# Schametic.net
KiCad netlist of a schematic drawn in EasyEDA
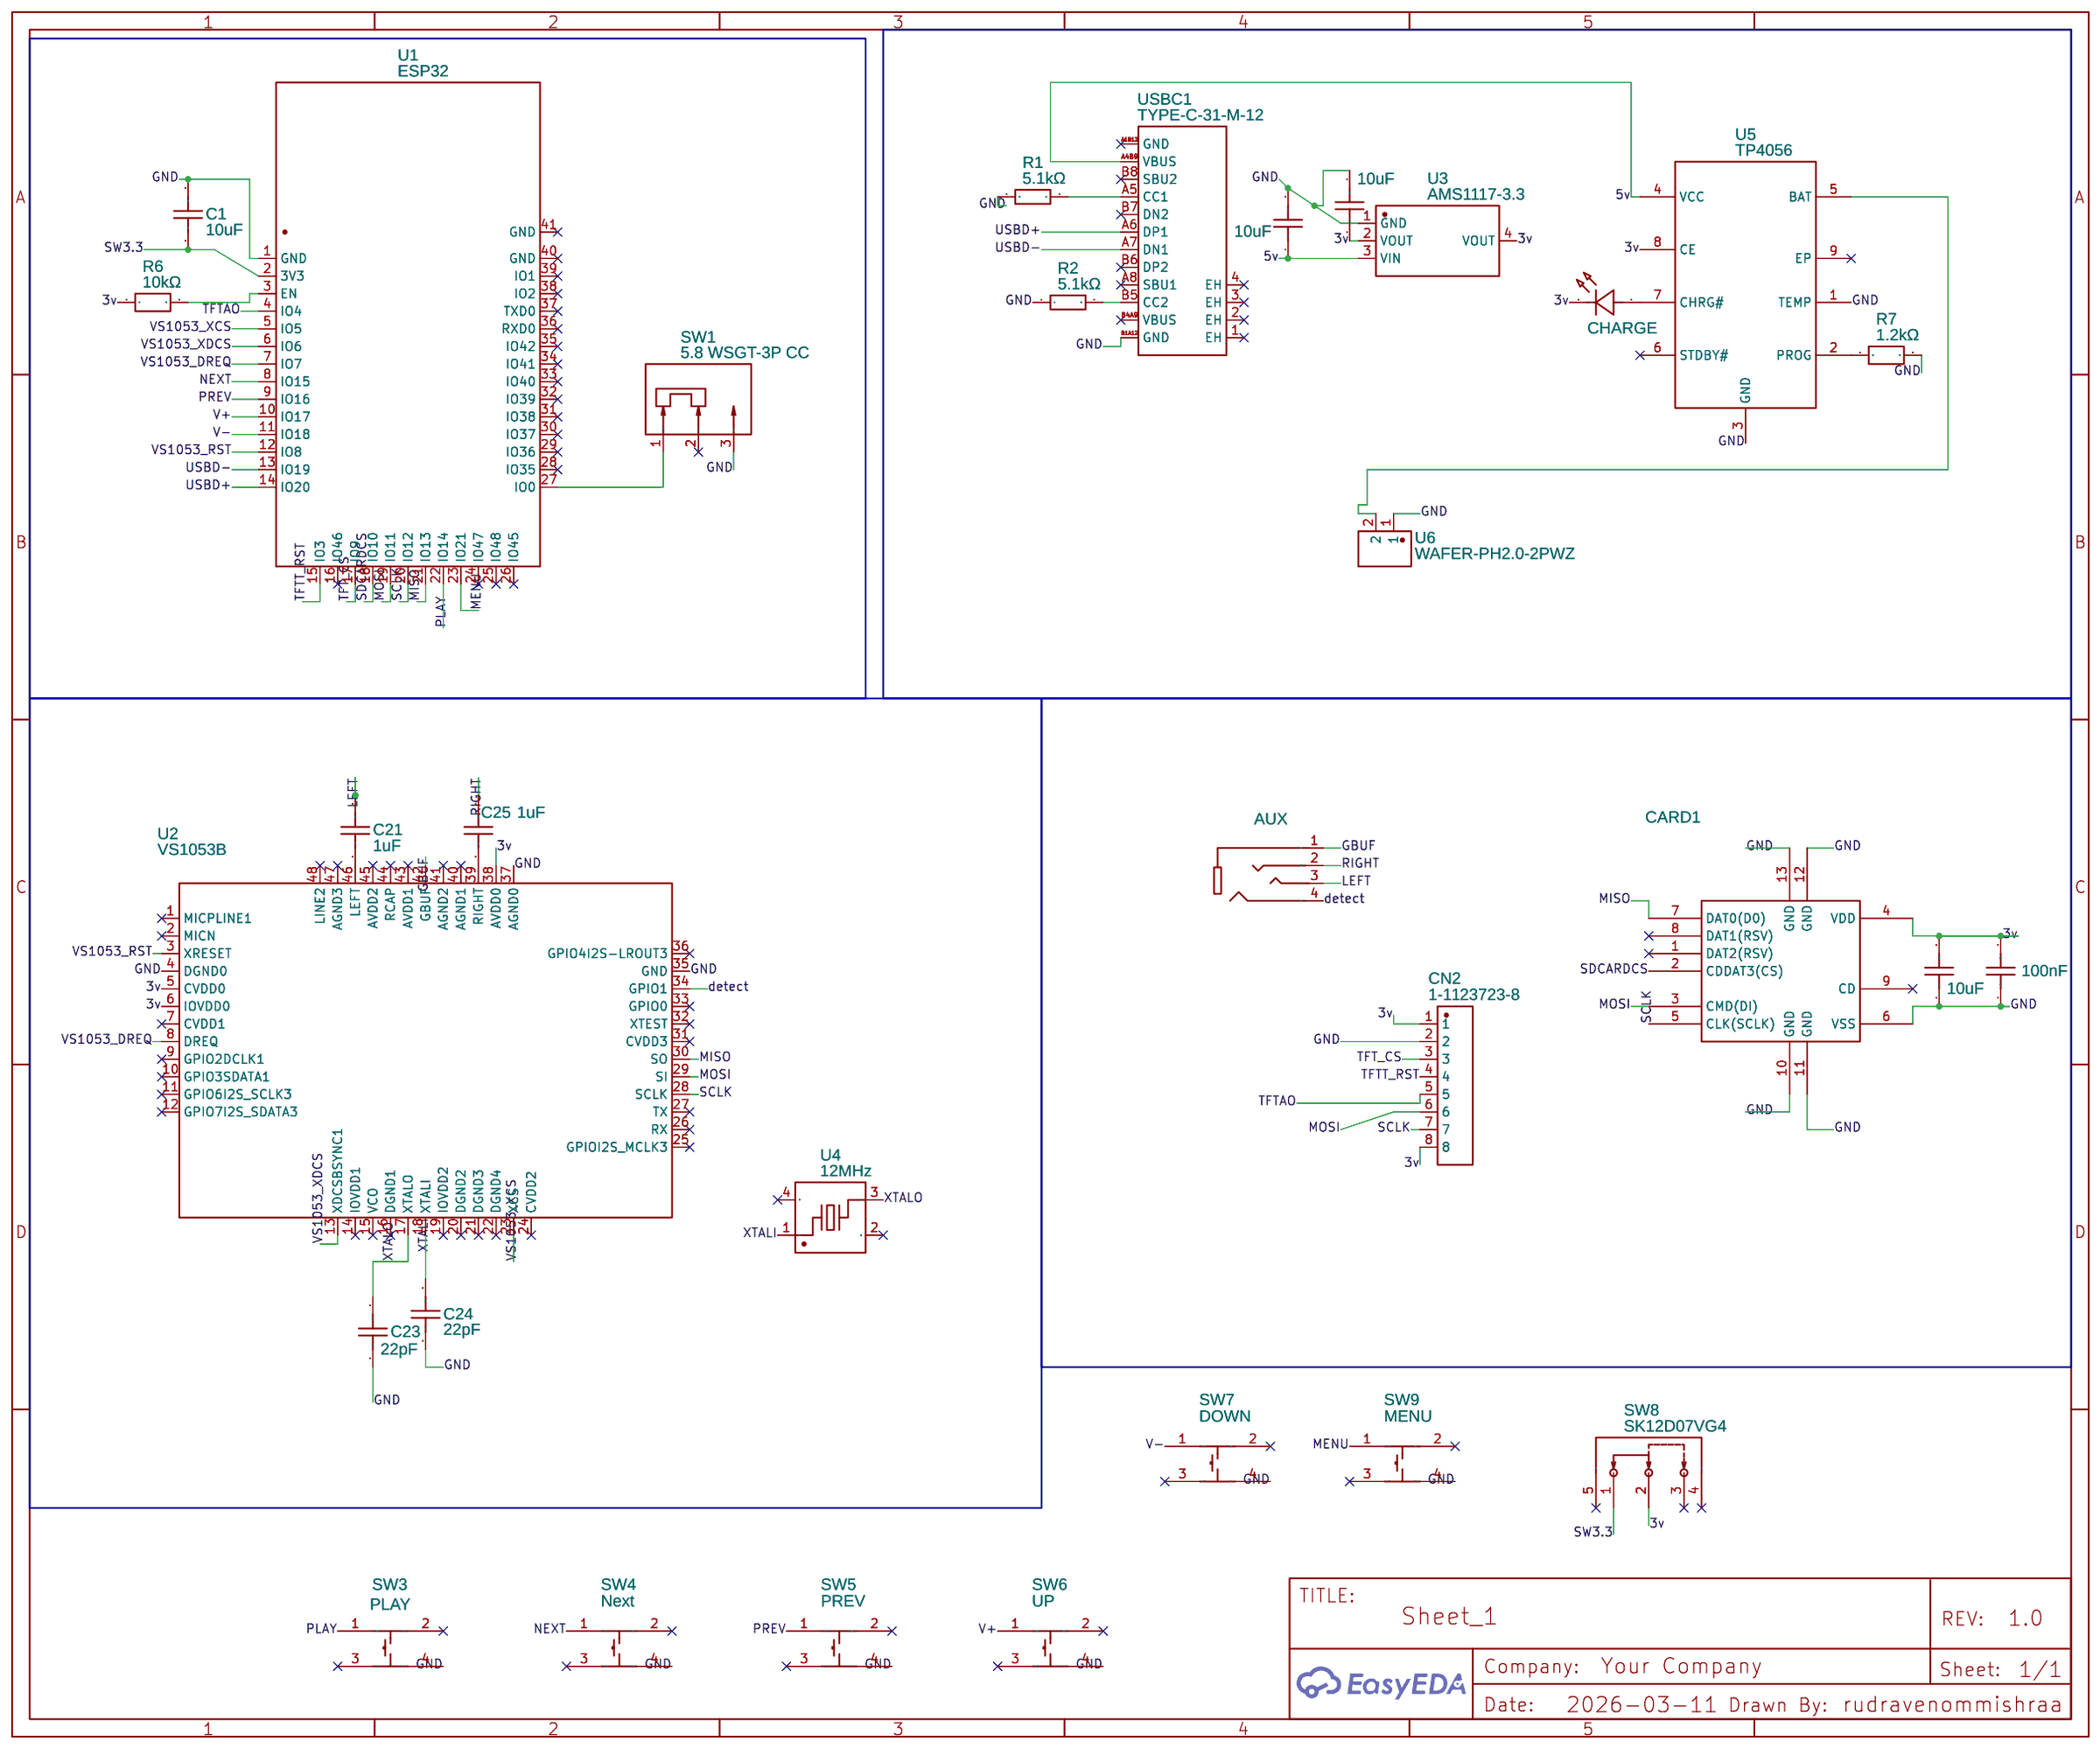
[diagram p0: schematic sheet]

(export (version "E")
  (design (tool "Eeschema 10.0.6"))
  (components
    (comp (ref "C1")
      (value "10uF")
      (fields
        (field (name "Manufacturer Part") "CL10A106KP8NNNC")
        (field (name "Manufacturer") "SAMSUNG(三星)")
      )
      (libsource (lib "") (part "CL10A106KP8NNNC"))
    )
    (comp (ref "C2")
      (value "10uF")
      (fields
        (field (name "Manufacturer Part") "CL10A106KP8NNNC")
        (field (name "Manufacturer") "SAMSUNG(三星)")
      )
      (libsource (lib "") (part "CL10A106KP8NNNC"))
    )
    (comp (ref "C7")
      (value "100nF")
      (fields
        (field (name "Manufacturer Part") "CC0603KRX7R9BB104")
        (field (name "Manufacturer") "YAGEO(国巨)")
      )
      (libsource (lib "") (part "CC0603KRX7R9BB104"))
    )
    (comp (ref "C9")
      (value "10uF")
      (fields
        (field (name "Manufacturer Part") "CL10A106KP8NNNC")
        (field (name "Manufacturer") "SAMSUNG(三星)")
      )
      (libsource (lib "") (part "CL10A106KP8NNNC"))
    )
    (comp (ref "C10")
      (value "10uF")
      (fields
        (field (name "Manufacturer Part") "CL10A106KP8NNNC")
        (field (name "Manufacturer") "SAMSUNG(三星)")
      )
      (libsource (lib "") (part "CL10A106KP8NNNC"))
    )
    (comp (ref "C21")
      (value "1uF")
      (fields
        (field (name "Manufacturer Part") "CL10A105KB8NNNC")
        (field (name "Manufacturer") "SAMSUNG(三星)")
      )
      (libsource (lib "") (part "CL10A105KB8NNNC_1"))
    )
    (comp (ref "C23")
      (value "22pF")
      (fields (field (name "Manufacturer Part") "04025A220KAT2A") (field (name "Manufacturer") "Kyocera AVX"))
      (libsource (lib "") (part "04025A220KAT2A"))
    )
    (comp (ref "C24")
      (value "22pF")
      (fields (field (name "Manufacturer Part") "04025A220KAT2A") (field (name "Manufacturer") "Kyocera AVX"))
      (libsource (lib "") (part "04025A220KAT2A"))
    )
    (comp (ref "C25")
      (value "1uF")
      (fields
        (field (name "Manufacturer Part") "CL10A105KB8NNNC")
        (field (name "Manufacturer") "SAMSUNG(三星)")
      )
      (libsource (lib "") (part "CL10A105KB8NNNC"))
    )
    (comp (ref "CARD1")
      (value "TF-01A")
      (fields (field (name "Manufacturer") "韩国韩荣"))
      (libsource (lib "") (part "TF-01A"))
    )
    (comp (ref "CHARGE")
      (value "15-21SURC/S530-A3/3T")
      (fields (field (name "Manufacturer") "EVERLIGHT(亿光)"))
      (libsource (lib "") (part "15-21SURC/S530-A3/3T"))
    )
    (comp (ref "CN1")
      (value "AUX")
      (fields (field (name "Manufacturer Part") "HC-PJ-320A") (field (name "Manufacturer") "HC(虹成电子)"))
      (libsource (lib "") (part "HC-PJ-320A"))
    )
    (comp (ref "CN2")
      (value "1-1123723-8")
      (fields (field (name "Manufacturer") "TE Connectivity(泰科电子)"))
      (libsource (lib "") (part "1-1123723-8"))
    )
    (comp (ref "R1")
      (value "5.1kΩ")
      (fields
        (field (name "Manufacturer Part") "0603WAF5101T5E")
        (field (name "Manufacturer") "UNI-ROYAL(厚声)")
      )
      (libsource (lib "") (part "0603WAF5101T5E"))
    )
    (comp (ref "R2")
      (value "5.1kΩ")
      (fields
        (field (name "Manufacturer Part") "0603WAF5101T5E")
        (field (name "Manufacturer") "UNI-ROYAL(厚声)")
      )
      (libsource (lib "") (part "0603WAF5101T5E"))
    )
    (comp (ref "R6")
      (value "10kΩ")
      (fields (field (name "Manufacturer Part") "SCR0603J10K") (field (name "Manufacturer") "VO(翔胜)"))
      (libsource (lib "") (part "SCR0603J10K"))
    )
    (comp (ref "R7")
      (value "1.2kΩ")
      (fields
        (field (name "Manufacturer Part") "0603WAD1201T5E")
        (field (name "Manufacturer") "UNI-ROYAL(厚声)")
      )
      (libsource (lib "") (part "0603WAD1201T5E"))
    )
    (comp (ref "SW1")
      (value "5.8 WSGT-3P CC")
      (fields (field (name "Manufacturer") "SHOU HAN(首韩)"))
      (libsource (lib "") (part "5.8 WSGT-3P CC"))
    )
    (comp (ref "SW3")
      (value "PLAY")
      (fields (field (name "Manufacturer Part") "TS-1002S-07026C") (field (name "Manufacturer") "XUNPU(讯普)"))
      (libsource (lib "") (part "TS-1002S-07026C"))
    )
    (comp (ref "SW4")
      (value "Next")
      (fields (field (name "Manufacturer Part") "TS-1002S-07026C") (field (name "Manufacturer") "XUNPU(讯普)"))
      (libsource (lib "") (part "TS-1002S-07026C"))
    )
    (comp (ref "SW5")
      (value "PREV")
      (fields (field (name "Manufacturer Part") "TS-1002S-07026C") (field (name "Manufacturer") "XUNPU(讯普)"))
      (libsource (lib "") (part "TS-1002S-07026C"))
    )
    (comp (ref "SW6")
      (value "UP")
      (fields (field (name "Manufacturer Part") "TS-1002S-07026C") (field (name "Manufacturer") "XUNPU(讯普)"))
      (libsource (lib "") (part "TS-1002S-07026C"))
    )
    (comp (ref "SW7")
      (value "DOWN")
      (fields (field (name "Manufacturer Part") "TS-1002S-07026C") (field (name "Manufacturer") "XUNPU(讯普)"))
      (libsource (lib "") (part "TS-1002S-07026C"))
    )
    (comp (ref "SW8")
      (value "SK12D07VG4")
      (fields (field (name "Manufacturer") "SHOU HAN(首韩)"))
      (libsource (lib "") (part "SK12D07VG4"))
    )
    (comp (ref "SW9")
      (value "MENU")
      (fields (field (name "Manufacturer Part") "TS-1002S-07026C") (field (name "Manufacturer") "XUNPU(讯普)"))
      (libsource (lib "") (part "TS-1002S-07026C"))
    )
    (comp (ref "U1")
      (value "ESP32")
      (fields
        (field (name "Manufacturer Part") "ESP32-S3-WROOM-1-N16R8")
        (field (name "Manufacturer") "ESPRESSIF(乐鑫)")
      )
      (libsource (lib "") (part "ESP32-S3-WROOM-1(N16R8)"))
    )
    (comp (ref "U2")
      (value "VS1053B")
      (fields (field (name "Manufacturer Part") "VS1053B-L") (field (name "Manufacturer") "VLSI"))
      (libsource (lib "") (part "VS1053B"))
    )
    (comp (ref "U3")
      (value "AMS1117-3.3")
      (fields (field (name "Manufacturer") "AMS"))
      (libsource (lib "") (part "AMS1117-3.3"))
    )
    (comp (ref "U4")
      (value "12MHz")
      (fields
        (field (name "Manufacturer Part") "01.X.MH.120HHRI0012000000")
        (field (name "Manufacturer") "CREC(晶宝)")
      )
      (libsource (lib "") (part "01.X.MH.120HHRI0012000000"))
    )
    (comp (ref "U5")
      (value "TP4056")
      (fields
        (field (name "Manufacturer Part") "TP4056-42-ESOP8")
        (field (name "Manufacturer") "TOPPOWER(南京拓微)")
      )
      (libsource (lib "") (part "TP4056"))
    )
    (comp (ref "U6")
      (value "WAFER-PH2.0-2PWZ")
      (fields (field (name "Manufacturer") "XUNPU(讯普)"))
      (libsource (lib "") (part "WAFER-PH2.0-2PWZ"))
    )
    (comp (ref "USBC1")
      (value "TYPE-C-31-M-12")
      (fields (field (name "Manufacturer") "韩国韩荣"))
      (libsource (lib "") (part "TYPE-C-31-M-12"))
    )
  )
  (nets
    (net (code "1") (name "/3v") (class "Default")
      (node (ref "C10") (pin "1") (pinfunction "1_1") (pintype "unspecified"))
      (node (ref "C2") (pin "2") (pinfunction "2_2") (pintype "unspecified"))
      (node (ref "C7") (pin "2") (pinfunction "2_2") (pintype "unspecified"))
      (node (ref "CARD1") (pin "4") (pinfunction "VDD_4") (pintype "input"))
      (node (ref "CHARGE") (pin "2") (pinfunction "K_2") (pintype "unspecified"))
      (node (ref "CN2") (pin "1") (pinfunction "1_1") (pintype "unspecified"))
      (node (ref "CN2") (pin "8") (pinfunction "8_8") (pintype "unspecified"))
      (node (ref "R6") (pin "1") (pinfunction "1_1") (pintype "unspecified"))
      (node (ref "SW8") (pin "2") (pinfunction "2_2") (pintype "unspecified"))
      (node (ref "U2") (pin "38") (pinfunction "AVDD0_38") (pintype "unspecified"))
      (node (ref "U2") (pin "5") (pinfunction "CVDD0_5") (pintype "passive"))
      (node (ref "U2") (pin "6") (pinfunction "IOVDD0_6") (pintype "passive"))
      (node (ref "U3") (pin "2") (pinfunction "VOUT_2") (pintype "unspecified"))
      (node (ref "U3") (pin "4") (pinfunction "VOUT_4") (pintype "unspecified"))
      (node (ref "U5") (pin "8") (pinfunction "CE_8") (pintype "unspecified"))
    )
    (net (code "2") (name "/5v") (class "Default")
      (node (ref "C9") (pin "1") (pinfunction "1_1") (pintype "unspecified"))
      (node (ref "U3") (pin "3") (pinfunction "VIN_3") (pintype "unspecified"))
      (node (ref "U5") (pin "4") (pinfunction "VCC_4") (pintype "unspecified"))
      (node (ref "USBC1") (pin "A4B9") (pinfunction "VBUS_A4B9") (pintype "unspecified"))
    )
    (net (code "3") (name "/GBUF") (class "Default")
      (node (ref "CN1") (pin "1") (pinfunction "1_1") (pintype "unspecified"))
      (node (ref "U2") (pin "42") (pinfunction "GBUF_42") (pintype "unspecified"))
    )
    (net (code "4") (name "/GND") (class "Default")
      (node (ref "C1") (pin "2") (pinfunction "2_2") (pintype "unspecified"))
      (node (ref "C10") (pin "2") (pinfunction "2_2") (pintype "unspecified"))
      (node (ref "C2") (pin "1") (pinfunction "1_1") (pintype "unspecified"))
      (node (ref "C23") (pin "1") (pinfunction "1_1") (pintype "unspecified"))
      (node (ref "C24") (pin "1") (pinfunction "1_1") (pintype "unspecified"))
      (node (ref "C7") (pin "1") (pinfunction "1_1") (pintype "unspecified"))
      (node (ref "C9") (pin "2") (pinfunction "2_2") (pintype "unspecified"))
      (node (ref "CARD1") (pin "10") (pinfunction "GND_10") (pintype "input"))
      (node (ref "CARD1") (pin "11") (pinfunction "GND_11") (pintype "input"))
      (node (ref "CARD1") (pin "12") (pinfunction "GND_12") (pintype "input"))
      (node (ref "CARD1") (pin "13") (pinfunction "GND_13") (pintype "input"))
      (node (ref "CARD1") (pin "6") (pinfunction "VSS_6") (pintype "input"))
      (node (ref "CN2") (pin "2") (pinfunction "2_2") (pintype "unspecified"))
      (node (ref "R1") (pin "1") (pinfunction "1_1") (pintype "input"))
      (node (ref "R2") (pin "1") (pinfunction "1_1") (pintype "input"))
      (node (ref "R7") (pin "2") (pinfunction "2_2") (pintype "unspecified"))
      (node (ref "SW1") (pin "3") (pinfunction "3_3") (pintype "unspecified"))
      (node (ref "SW3") (pin "4") (pinfunction "4_4") (pintype "unspecified"))
      (node (ref "SW4") (pin "4") (pinfunction "4_4") (pintype "unspecified"))
      (node (ref "SW5") (pin "4") (pinfunction "4_4") (pintype "unspecified"))
      (node (ref "SW6") (pin "4") (pinfunction "4_4") (pintype "unspecified"))
      (node (ref "SW7") (pin "4") (pinfunction "4_4") (pintype "unspecified"))
      (node (ref "SW9") (pin "4") (pinfunction "4_4") (pintype "unspecified"))
      (node (ref "U1") (pin "1") (pinfunction "GND_1") (pintype "unspecified"))
      (node (ref "U2") (pin "35") (pinfunction "GND_35") (pintype "unspecified"))
      (node (ref "U2") (pin "37") (pinfunction "AGND0_37") (pintype "unspecified"))
      (node (ref "U2") (pin "4") (pinfunction "DGND0_4") (pintype "unspecified"))
      (node (ref "U3") (pin "1") (pinfunction "GND_1") (pintype "unspecified"))
      (node (ref "U5") (pin "1") (pinfunction "TEMP_1") (pintype "unspecified"))
      (node (ref "U5") (pin "3") (pinfunction "GND_3") (pintype "unspecified"))
      (node (ref "U6") (pin "1") (pinfunction "1_1") (pintype "unspecified"))
      (node (ref "USBC1") (pin "B1A12") (pinfunction "GND_B1A12") (pintype "unspecified"))
    )
    (net (code "5") (name "/LEFT") (class "Default")
      (node (ref "C21") (pin "2") (pinfunction "2_2") (pintype "unspecified"))
      (node (ref "CN1") (pin "3") (pinfunction "3_3") (pintype "unspecified"))
    )
    (net (code "6") (name "/MENU") (class "Default")
      (node (ref "SW9") (pin "1") (pinfunction "1_1") (pintype "unspecified"))
      (node (ref "U1") (pin "23") (pinfunction "IO21_23") (pintype "unspecified"))
    )
    (net (code "7") (name "/MISO") (class "Default")
      (node (ref "CARD1") (pin "7") (pinfunction "DAT0(D0)_7") (pintype "bidirectional"))
      (node (ref "U1") (pin "21") (pinfunction "IO13_21") (pintype "unspecified"))
      (node (ref "U2") (pin "30") (pinfunction "SO_30") (pintype "unspecified"))
    )
    (net (code "8") (name "/MOSI") (class "Default")
      (node (ref "CARD1") (pin "3") (pinfunction "CMD(DI)_3") (pintype "input"))
      (node (ref "CN2") (pin "6") (pinfunction "6_6") (pintype "unspecified"))
      (node (ref "U1") (pin "19") (pinfunction "IO11_19") (pintype "unspecified"))
      (node (ref "U2") (pin "29") (pinfunction "SI_29") (pintype "unspecified"))
    )
    (net (code "9") (name "/NEXT") (class "Default")
      (node (ref "SW4") (pin "1") (pinfunction "1_1") (pintype "unspecified"))
      (node (ref "U1") (pin "8") (pinfunction "IO15_8") (pintype "unspecified"))
    )
    (net (code "10") (name "/PLAY") (class "Default")
      (node (ref "SW3") (pin "1") (pinfunction "1_1") (pintype "unspecified"))
      (node (ref "U1") (pin "22") (pinfunction "IO14_22") (pintype "unspecified"))
    )
    (net (code "11") (name "/PREV") (class "Default")
      (node (ref "SW5") (pin "1") (pinfunction "1_1") (pintype "unspecified"))
      (node (ref "U1") (pin "9") (pinfunction "IO16_9") (pintype "unspecified"))
    )
    (net (code "12") (name "/RIGHT") (class "Default")
      (node (ref "C25") (pin "1") (pinfunction "1_1") (pintype "unspecified"))
      (node (ref "CN1") (pin "2") (pinfunction "2_2") (pintype "unspecified"))
    )
    (net (code "13") (name "/SCLK") (class "Default")
      (node (ref "CARD1") (pin "5") (pinfunction "CLK(SCLK)_5") (pintype "input"))
      (node (ref "CN2") (pin "7") (pinfunction "7_7") (pintype "unspecified"))
      (node (ref "U1") (pin "20") (pinfunction "IO12_20") (pintype "unspecified"))
      (node (ref "U2") (pin "28") (pinfunction "SCLK_28") (pintype "unspecified"))
    )
    (net (code "14") (name "/SDCARDCS") (class "Default")
      (node (ref "CARD1") (pin "2") (pinfunction "CDDAT3(CS)_2") (pintype "bidirectional"))
      (node (ref "U1") (pin "18") (pinfunction "IO10_18") (pintype "unspecified"))
    )
    (net (code "15") (name "/SW3.3") (class "Default")
      (node (ref "C1") (pin "1") (pinfunction "1_1") (pintype "unspecified"))
      (node (ref "SW8") (pin "1") (pinfunction "1_1") (pintype "unspecified"))
      (node (ref "U1") (pin "2") (pinfunction "3V3_2") (pintype "unspecified"))
    )
    (net (code "16") (name "/TFTAO") (class "Default")
      (node (ref "CN2") (pin "5") (pinfunction "5_5") (pintype "unspecified"))
      (node (ref "U1") (pin "4") (pinfunction "IO4_4") (pintype "unspecified"))
    )
    (net (code "17") (name "/TFTT_RST") (class "Default")
      (node (ref "CN2") (pin "4") (pinfunction "4_4") (pintype "unspecified"))
      (node (ref "U1") (pin "15") (pinfunction "IO3_15") (pintype "unspecified"))
    )
    (net (code "18") (name "/TFT_CS") (class "Default")
      (node (ref "CN2") (pin "3") (pinfunction "3_3") (pintype "unspecified"))
      (node (ref "U1") (pin "17") (pinfunction "IO9_17") (pintype "unspecified"))
    )
    (net (code "19") (name "/USBD+") (class "Default")
      (node (ref "U1") (pin "14") (pinfunction "IO20_14") (pintype "unspecified"))
      (node (ref "USBC1") (pin "A6") (pinfunction "DP1_A6") (pintype "unspecified"))
    )
    (net (code "20") (name "/USBD-") (class "Default")
      (node (ref "U1") (pin "13") (pinfunction "IO19_13") (pintype "unspecified"))
      (node (ref "USBC1") (pin "A7") (pinfunction "DN1_A7") (pintype "unspecified"))
    )
    (net (code "21") (name "/V+") (class "Default")
      (node (ref "SW6") (pin "1") (pinfunction "1_1") (pintype "unspecified"))
      (node (ref "U1") (pin "10") (pinfunction "IO17_10") (pintype "unspecified"))
    )
    (net (code "22") (name "/V-") (class "Default")
      (node (ref "SW7") (pin "1") (pinfunction "1_1") (pintype "unspecified"))
      (node (ref "U1") (pin "11") (pinfunction "IO18_11") (pintype "unspecified"))
    )
    (net (code "23") (name "/VS1053_DREQ") (class "Default")
      (node (ref "U1") (pin "7") (pinfunction "IO7_7") (pintype "unspecified"))
      (node (ref "U2") (pin "8") (pinfunction "DREQ_8") (pintype "unspecified"))
    )
    (net (code "24") (name "/VS1053_RST") (class "Default")
      (node (ref "U1") (pin "12") (pinfunction "IO8_12") (pintype "unspecified"))
      (node (ref "U2") (pin "3") (pinfunction "XRESET_3") (pintype "unspecified"))
    )
    (net (code "25") (name "/VS1053_XCS") (class "Default")
      (node (ref "U1") (pin "5") (pinfunction "IO5_5") (pintype "unspecified"))
      (node (ref "U2") (pin "23") (pinfunction "XCS_23") (pintype "unspecified"))
    )
    (net (code "26") (name "/VS1053_XDCS") (class "Default")
      (node (ref "U1") (pin "6") (pinfunction "IO6_6") (pintype "unspecified"))
      (node (ref "U2") (pin "13") (pinfunction "XDCSBSYNC1_13") (pintype "unspecified"))
    )
    (net (code "27") (name "/XTALI") (class "Default")
      (node (ref "C24") (pin "2") (pinfunction "2_2") (pintype "unspecified"))
      (node (ref "U2") (pin "18") (pinfunction "XTALI_18") (pintype "unspecified"))
      (node (ref "U4") (pin "1") (pinfunction "1_1") (pintype "input"))
    )
    (net (code "28") (name "/XTALO") (class "Default")
      (node (ref "C23") (pin "2") (pinfunction "2_2") (pintype "unspecified"))
      (node (ref "U2") (pin "17") (pinfunction "XTALO_17") (pintype "unspecified"))
      (node (ref "U4") (pin "3") (pinfunction "3_3") (pintype "input"))
    )
    (net (code "29") (name "/detect") (class "Default")
      (node (ref "CN1") (pin "4") (pinfunction "4_4") (pintype "unspecified"))
      (node (ref "U2") (pin "34") (pinfunction "GPIO1_34") (pintype "unspecified"))
    )
    (net (code "30") (name "Net-(CHARGE-A)") (class "Default")
      (node (ref "CHARGE") (pin "1") (pinfunction "A_1") (pintype "unspecified"))
      (node (ref "U5") (pin "7") (pinfunction "CHRG#_7") (pintype "unspecified"))
    )
    (net (code "31") (name "Net-(U1-EN)") (class "Default")
      (node (ref "R6") (pin "2") (pinfunction "2_2") (pintype "unspecified"))
      (node (ref "U1") (pin "3") (pinfunction "EN_3") (pintype "unspecified"))
    )
    (net (code "32") (name "Net-(U1-IO0)") (class "Default")
      (node (ref "SW1") (pin "1") (pinfunction "1_1") (pintype "unspecified"))
      (node (ref "U1") (pin "27") (pinfunction "IO0_27") (pintype "unspecified"))
    )
    (net (code "33") (name "Net-(U2-LEFT)") (class "Default")
      (node (ref "C21") (pin "1") (pinfunction "1_1") (pintype "unspecified"))
      (node (ref "U2") (pin "46") (pinfunction "LEFT_46") (pintype "unspecified"))
    )
    (net (code "34") (name "Net-(U2-RIGHT)") (class "Default")
      (node (ref "C25") (pin "2") (pinfunction "2_2") (pintype "unspecified"))
      (node (ref "U2") (pin "39") (pinfunction "RIGHT_39") (pintype "unspecified"))
    )
    (net (code "35") (name "Net-(U5-BAT)") (class "Default")
      (node (ref "U5") (pin "5") (pinfunction "BAT_5") (pintype "unspecified"))
      (node (ref "U6") (pin "2") (pinfunction "2_2") (pintype "unspecified"))
    )
    (net (code "36") (name "Net-(U5-PROG)") (class "Default")
      (node (ref "R7") (pin "1") (pinfunction "1_1") (pintype "unspecified"))
      (node (ref "U5") (pin "2") (pinfunction "PROG_2") (pintype "unspecified"))
    )
    (net (code "37") (name "Net-(USBC1-CC1)") (class "Default")
      (node (ref "R1") (pin "2") (pinfunction "2_2") (pintype "input"))
      (node (ref "USBC1") (pin "A5") (pinfunction "CC1_A5") (pintype "unspecified"))
    )
    (net (code "38") (name "Net-(USBC1-CC2)") (class "Default")
      (node (ref "R2") (pin "2") (pinfunction "2_2") (pintype "input"))
      (node (ref "USBC1") (pin "B5") (pinfunction "CC2_B5") (pintype "unspecified"))
    )
    (net (code "39") (name "unconnected-(CARD1-CD-Pad9)") (class "Default")
      (node (ref "CARD1") (pin "9") (pinfunction "CD_9") (pintype "input+no_connect"))
    )
    (net (code "40") (name "unconnected-(CARD1-DAT1(RSV)-Pad8)") (class "Default")
      (node (ref "CARD1") (pin "8") (pinfunction "DAT1(RSV)_8") (pintype "bidirectional+no_connect"))
    )
    (net (code "41") (name "unconnected-(CARD1-DAT2(RSV)-Pad1)") (class "Default")
      (node (ref "CARD1") (pin "1") (pinfunction "DAT2(RSV)_1") (pintype "bidirectional+no_connect"))
    )
    (net (code "42") (name "unconnected-(SW1-Pad2)") (class "Default")
      (node (ref "SW1") (pin "2") (pinfunction "2_2") (pintype "unspecified+no_connect"))
    )
    (net (code "43") (name "unconnected-(SW3-Pad2)") (class "Default")
      (node (ref "SW3") (pin "2") (pinfunction "2_2") (pintype "unspecified+no_connect"))
    )
    (net (code "44") (name "unconnected-(SW3-Pad3)") (class "Default")
      (node (ref "SW3") (pin "3") (pinfunction "3_3") (pintype "unspecified+no_connect"))
    )
    (net (code "45") (name "unconnected-(SW4-Pad2)") (class "Default")
      (node (ref "SW4") (pin "2") (pinfunction "2_2") (pintype "unspecified+no_connect"))
    )
    (net (code "46") (name "unconnected-(SW4-Pad3)") (class "Default")
      (node (ref "SW4") (pin "3") (pinfunction "3_3") (pintype "unspecified+no_connect"))
    )
    (net (code "47") (name "unconnected-(SW5-Pad2)") (class "Default")
      (node (ref "SW5") (pin "2") (pinfunction "2_2") (pintype "unspecified+no_connect"))
    )
    (net (code "48") (name "unconnected-(SW5-Pad3)") (class "Default")
      (node (ref "SW5") (pin "3") (pinfunction "3_3") (pintype "unspecified+no_connect"))
    )
    (net (code "49") (name "unconnected-(SW6-Pad2)") (class "Default")
      (node (ref "SW6") (pin "2") (pinfunction "2_2") (pintype "unspecified+no_connect"))
    )
    (net (code "50") (name "unconnected-(SW6-Pad3)") (class "Default")
      (node (ref "SW6") (pin "3") (pinfunction "3_3") (pintype "unspecified+no_connect"))
    )
    (net (code "51") (name "unconnected-(SW7-Pad2)") (class "Default")
      (node (ref "SW7") (pin "2") (pinfunction "2_2") (pintype "unspecified+no_connect"))
    )
    (net (code "52") (name "unconnected-(SW7-Pad3)") (class "Default")
      (node (ref "SW7") (pin "3") (pinfunction "3_3") (pintype "unspecified+no_connect"))
    )
    (net (code "53") (name "unconnected-(SW8-Pad3)") (class "Default")
      (node (ref "SW8") (pin "3") (pinfunction "3_3") (pintype "unspecified+no_connect"))
    )
    (net (code "54") (name "unconnected-(SW8-Pad4)") (class "Default")
      (node (ref "SW8") (pin "4") (pinfunction "4_4") (pintype "unspecified+no_connect"))
    )
    (net (code "55") (name "unconnected-(SW8-Pad5)") (class "Default")
      (node (ref "SW8") (pin "5") (pinfunction "5_5") (pintype "unspecified+no_connect"))
    )
    (net (code "56") (name "unconnected-(SW9-Pad2)") (class "Default")
      (node (ref "SW9") (pin "2") (pinfunction "2_2") (pintype "unspecified+no_connect"))
    )
    (net (code "57") (name "unconnected-(SW9-Pad3)") (class "Default")
      (node (ref "SW9") (pin "3") (pinfunction "3_3") (pintype "unspecified+no_connect"))
    )
    (net (code "58") (name "unconnected-(U1-GND-Pad40)") (class "Default")
      (node (ref "U1") (pin "40") (pinfunction "GND_40") (pintype "unspecified+no_connect"))
    )
    (net (code "59") (name "unconnected-(U1-GND-Pad41)") (class "Default")
      (node (ref "U1") (pin "41") (pinfunction "GND_41") (pintype "unspecified+no_connect"))
    )
    (net (code "60") (name "unconnected-(U1-IO1-Pad39)") (class "Default")
      (node (ref "U1") (pin "39") (pinfunction "IO1_39") (pintype "unspecified+no_connect"))
    )
    (net (code "61") (name "unconnected-(U1-IO2-Pad38)") (class "Default")
      (node (ref "U1") (pin "38") (pinfunction "IO2_38") (pintype "unspecified+no_connect"))
    )
    (net (code "62") (name "unconnected-(U1-IO35-Pad28)") (class "Default")
      (node (ref "U1") (pin "28") (pinfunction "IO35_28") (pintype "unspecified+no_connect"))
    )
    (net (code "63") (name "unconnected-(U1-IO36-Pad29)") (class "Default")
      (node (ref "U1") (pin "29") (pinfunction "IO36_29") (pintype "unspecified+no_connect"))
    )
    (net (code "64") (name "unconnected-(U1-IO37-Pad30)") (class "Default")
      (node (ref "U1") (pin "30") (pinfunction "IO37_30") (pintype "unspecified+no_connect"))
    )
    (net (code "65") (name "unconnected-(U1-IO38-Pad31)") (class "Default")
      (node (ref "U1") (pin "31") (pinfunction "IO38_31") (pintype "unspecified+no_connect"))
    )
    (net (code "66") (name "unconnected-(U1-IO39-Pad32)") (class "Default")
      (node (ref "U1") (pin "32") (pinfunction "IO39_32") (pintype "unspecified+no_connect"))
    )
    (net (code "67") (name "unconnected-(U1-IO40-Pad33)") (class "Default")
      (node (ref "U1") (pin "33") (pinfunction "IO40_33") (pintype "unspecified+no_connect"))
    )
    (net (code "68") (name "unconnected-(U1-IO41-Pad34)") (class "Default")
      (node (ref "U1") (pin "34") (pinfunction "IO41_34") (pintype "unspecified+no_connect"))
    )
    (net (code "69") (name "unconnected-(U1-IO42-Pad35)") (class "Default")
      (node (ref "U1") (pin "35") (pinfunction "IO42_35") (pintype "unspecified+no_connect"))
    )
    (net (code "70") (name "unconnected-(U1-IO45-Pad26)") (class "Default")
      (node (ref "U1") (pin "26") (pinfunction "IO45_26") (pintype "unspecified+no_connect"))
    )
    (net (code "71") (name "unconnected-(U1-IO46-Pad16)") (class "Default")
      (node (ref "U1") (pin "16") (pinfunction "IO46_16") (pintype "unspecified+no_connect"))
    )
    (net (code "72") (name "unconnected-(U1-IO47-Pad24)") (class "Default")
      (node (ref "U1") (pin "24") (pinfunction "IO47_24") (pintype "unspecified+no_connect"))
    )
    (net (code "73") (name "unconnected-(U1-IO48-Pad25)") (class "Default")
      (node (ref "U1") (pin "25") (pinfunction "IO48_25") (pintype "unspecified+no_connect"))
    )
    (net (code "74") (name "unconnected-(U1-RXD0-Pad36)") (class "Default")
      (node (ref "U1") (pin "36") (pinfunction "RXD0_36") (pintype "unspecified+no_connect"))
    )
    (net (code "75") (name "unconnected-(U1-TXD0-Pad37)") (class "Default")
      (node (ref "U1") (pin "37") (pinfunction "TXD0_37") (pintype "unspecified+no_connect"))
    )
    (net (code "76") (name "unconnected-(U2-AGND1-Pad40)") (class "Default")
      (node (ref "U2") (pin "40") (pinfunction "AGND1_40") (pintype "unspecified+no_connect"))
    )
    (net (code "77") (name "unconnected-(U2-AGND2-Pad41)") (class "Default")
      (node (ref "U2") (pin "41") (pinfunction "AGND2_41") (pintype "unspecified+no_connect"))
    )
    (net (code "78") (name "unconnected-(U2-AGND3-Pad47)") (class "Default")
      (node (ref "U2") (pin "47") (pinfunction "AGND3_47") (pintype "unspecified+no_connect"))
    )
    (net (code "79") (name "unconnected-(U2-AVDD1-Pad43)") (class "Default")
      (node (ref "U2") (pin "43") (pinfunction "AVDD1_43") (pintype "passive+no_connect"))
    )
    (net (code "80") (name "unconnected-(U2-AVDD2-Pad45)") (class "Default")
      (node (ref "U2") (pin "45") (pinfunction "AVDD2_45") (pintype "passive+no_connect"))
    )
    (net (code "81") (name "unconnected-(U2-CVDD1-Pad7)") (class "Default")
      (node (ref "U2") (pin "7") (pinfunction "CVDD1_7") (pintype "passive+no_connect"))
    )
    (net (code "82") (name "unconnected-(U2-CVDD2-Pad24)") (class "Default")
      (node (ref "U2") (pin "24") (pinfunction "CVDD2_24") (pintype "passive+no_connect"))
    )
    (net (code "83") (name "unconnected-(U2-CVDD3-Pad31)") (class "Default")
      (node (ref "U2") (pin "31") (pinfunction "CVDD3_31") (pintype "passive+no_connect"))
    )
    (net (code "84") (name "unconnected-(U2-DGND1-Pad16)") (class "Default")
      (node (ref "U2") (pin "16") (pinfunction "DGND1_16") (pintype "unspecified+no_connect"))
    )
    (net (code "85") (name "unconnected-(U2-DGND2-Pad20)") (class "Default")
      (node (ref "U2") (pin "20") (pinfunction "DGND2_20") (pintype "unspecified+no_connect"))
    )
    (net (code "86") (name "unconnected-(U2-DGND3-Pad21)") (class "Default")
      (node (ref "U2") (pin "21") (pinfunction "DGND3_21") (pintype "unspecified+no_connect"))
    )
    (net (code "87") (name "unconnected-(U2-DGND4-Pad22)") (class "Default")
      (node (ref "U2") (pin "22") (pinfunction "DGND4_22") (pintype "unspecified+no_connect"))
    )
    (net (code "88") (name "unconnected-(U2-GPIO0-Pad33)") (class "Default")
      (node (ref "U2") (pin "33") (pinfunction "GPIO0_33") (pintype "unspecified+no_connect"))
    )
    (net (code "89") (name "unconnected-(U2-GPIO2DCLK1-Pad9)") (class "Default")
      (node (ref "U2") (pin "9") (pinfunction "GPIO2DCLK1_9") (pintype "unspecified+no_connect"))
    )
    (net (code "90") (name "unconnected-(U2-GPIO3SDATA1-Pad10)") (class "Default")
      (node (ref "U2") (pin "10") (pinfunction "GPIO3SDATA1_10") (pintype "unspecified+no_connect"))
    )
    (net (code "91") (name "unconnected-(U2-GPIO4I2S-LROUT3-Pad36)") (class "Default")
      (node (ref "U2") (pin "36") (pinfunction "GPIO4I2S-LROUT3_36") (pintype "unspecified+no_connect"))
    )
    (net (code "92") (name "unconnected-(U2-GPIO6I2S_SCLK3-Pad11)") (class "Default")
      (node (ref "U2") (pin "11") (pinfunction "GPIO6I2S_SCLK3_11") (pintype "unspecified+no_connect"))
    )
    (net (code "93") (name "unconnected-(U2-GPIO7I2S_SDATA3-Pad12)") (class "Default")
      (node (ref "U2") (pin "12") (pinfunction "GPIO7I2S_SDATA3_12") (pintype "unspecified+no_connect"))
    )
    (net (code "94") (name "unconnected-(U2-GPIOI2S_MCLK3-Pad25)") (class "Default")
      (node (ref "U2") (pin "25") (pinfunction "GPIOI2S_MCLK3_25") (pintype "unspecified+no_connect"))
    )
    (net (code "95") (name "unconnected-(U2-IOVDD1-Pad14)") (class "Default")
      (node (ref "U2") (pin "14") (pinfunction "IOVDD1_14") (pintype "passive+no_connect"))
    )
    (net (code "96") (name "unconnected-(U2-IOVDD2-Pad19)") (class "Default")
      (node (ref "U2") (pin "19") (pinfunction "IOVDD2_19") (pintype "passive+no_connect"))
    )
    (net (code "97") (name "unconnected-(U2-LINE2-Pad48)") (class "Default")
      (node (ref "U2") (pin "48") (pinfunction "LINE2_48") (pintype "unspecified+no_connect"))
    )
    (net (code "98") (name "unconnected-(U2-MICN-Pad2)") (class "Default")
      (node (ref "U2") (pin "2") (pinfunction "MICN_2") (pintype "unspecified+no_connect"))
    )
    (net (code "99") (name "unconnected-(U2-MICPLINE1-Pad1)") (class "Default")
      (node (ref "U2") (pin "1") (pinfunction "MICPLINE1_1") (pintype "unspecified+no_connect"))
    )
    (net (code "100") (name "unconnected-(U2-RCAP-Pad44)") (class "Default")
      (node (ref "U2") (pin "44") (pinfunction "RCAP_44") (pintype "unspecified+no_connect"))
    )
    (net (code "101") (name "unconnected-(U2-RX-Pad26)") (class "Default")
      (node (ref "U2") (pin "26") (pinfunction "RX_26") (pintype "unspecified+no_connect"))
    )
    (net (code "102") (name "unconnected-(U2-TX-Pad27)") (class "Default")
      (node (ref "U2") (pin "27") (pinfunction "TX_27") (pintype "unspecified+no_connect"))
    )
    (net (code "103") (name "unconnected-(U2-VCO-Pad15)") (class "Default")
      (node (ref "U2") (pin "15") (pinfunction "VCO_15") (pintype "passive+no_connect"))
    )
    (net (code "104") (name "unconnected-(U2-XTEST-Pad32)") (class "Default")
      (node (ref "U2") (pin "32") (pinfunction "XTEST_32") (pintype "unspecified+no_connect"))
    )
    (net (code "105") (name "unconnected-(U4-GND-Pad2)") (class "Default")
      (node (ref "U4") (pin "2") (pinfunction "GND_2") (pintype "input+no_connect"))
    )
    (net (code "106") (name "unconnected-(U4-GND-Pad4)") (class "Default")
      (node (ref "U4") (pin "4") (pinfunction "GND_4") (pintype "input+no_connect"))
    )
    (net (code "107") (name "unconnected-(U5-EP-Pad9)") (class "Default")
      (node (ref "U5") (pin "9") (pinfunction "EP_9") (pintype "unspecified+no_connect"))
    )
    (net (code "108") (name "unconnected-(U5-STDBY#-Pad6)") (class "Default")
      (node (ref "U5") (pin "6") (pinfunction "STDBY#_6") (pintype "unspecified+no_connect"))
    )
    (net (code "109") (name "unconnected-(USBC1-DN2-PadB7)") (class "Default")
      (node (ref "USBC1") (pin "B7") (pinfunction "DN2_B7") (pintype "unspecified+no_connect"))
    )
    (net (code "110") (name "unconnected-(USBC1-DP2-PadB6)") (class "Default")
      (node (ref "USBC1") (pin "B6") (pinfunction "DP2_B6") (pintype "unspecified+no_connect"))
    )
    (net (code "111") (name "unconnected-(USBC1-EH-Pad1)") (class "Default")
      (node (ref "USBC1") (pin "1") (pinfunction "EH_1") (pintype "unspecified+no_connect"))
    )
    (net (code "112") (name "unconnected-(USBC1-EH-Pad2)") (class "Default")
      (node (ref "USBC1") (pin "2") (pinfunction "EH_2") (pintype "unspecified+no_connect"))
    )
    (net (code "113") (name "unconnected-(USBC1-EH-Pad3)") (class "Default")
      (node (ref "USBC1") (pin "3") (pinfunction "EH_3") (pintype "unspecified+no_connect"))
    )
    (net (code "114") (name "unconnected-(USBC1-EH-Pad4)") (class "Default")
      (node (ref "USBC1") (pin "4") (pinfunction "EH_4") (pintype "unspecified+no_connect"))
    )
    (net (code "115") (name "unconnected-(USBC1-GND-PadA1B12)") (class "Default")
      (node (ref "USBC1") (pin "A1B12") (pinfunction "GND_A1B12") (pintype "unspecified+no_connect"))
    )
    (net (code "116") (name "unconnected-(USBC1-SBU1-PadA8)") (class "Default")
      (node (ref "USBC1") (pin "A8") (pinfunction "SBU1_A8") (pintype "unspecified+no_connect"))
    )
    (net (code "117") (name "unconnected-(USBC1-SBU2-PadB8)") (class "Default")
      (node (ref "USBC1") (pin "B8") (pinfunction "SBU2_B8") (pintype "unspecified+no_connect"))
    )
    (net (code "118") (name "unconnected-(USBC1-VBUS-PadB4A9)") (class "Default")
      (node (ref "USBC1") (pin "B4A9") (pinfunction "VBUS_B4A9") (pintype "unspecified+no_connect"))
    )
  )
)
